# ArduinoUnoShield.net
KiCad netlist of a schematic drawn in Altium Designer
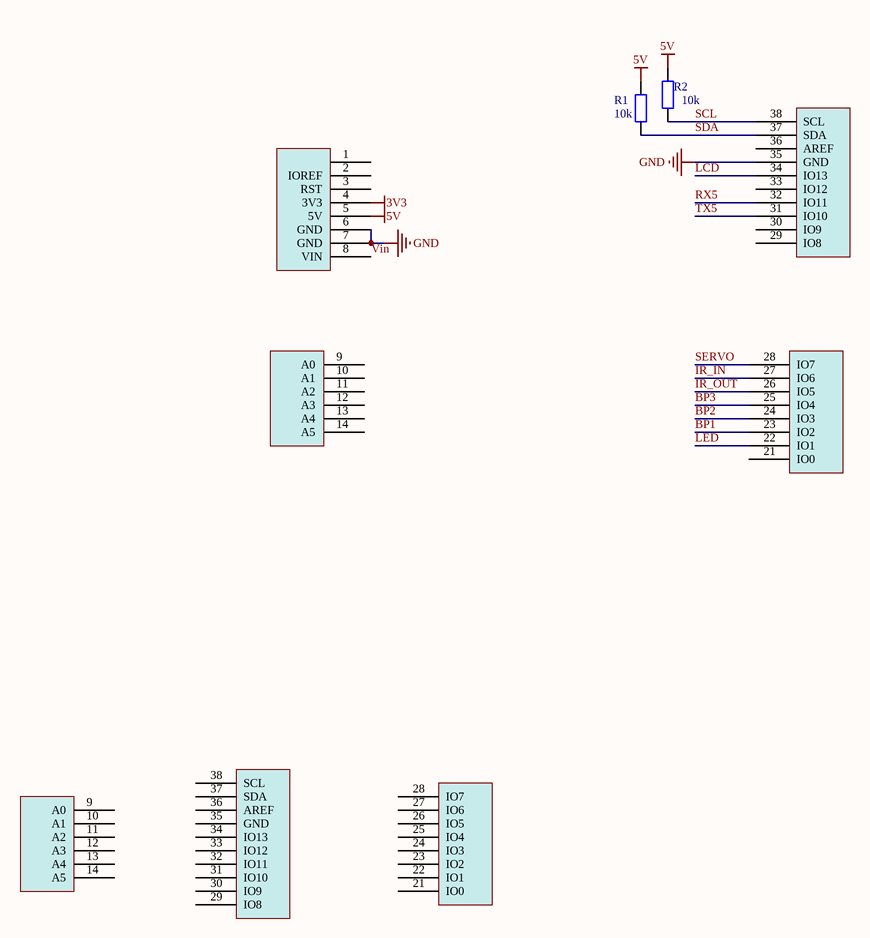
[diagram p0: ArduinoUnoShield.SchDoc]

(export (version "E")
  (design (tool "Eeschema 10.0.6"))
  (components
    (comp (ref "P1")
      (value "UNO4NUCLEO")
      (footprint "UNO4NUCLEO")
      (description "Header mâle, Carte-à-carte, 2.54 mm, 1 Rangée(s), 10 Contact(s), Traversant, droit, Série 2211S")
      (libsource (lib "MGLib_v2") (part "UNO4NUCLEO"))
    )
    (comp (ref "P1B")
      (value "UNO4NUCLEO")
      (footprint "UNO4NUCLEO")
      (description "Header mâle, Carte-à-carte, 2.54 mm, 1 Rangée(s), 10 Contact(s), Traversant, droit, Série 2211S")
      (libsource (lib "MGLib_v2") (part "UNO4NUCLEO"))
    )
    (comp (ref "P1C")
      (value "UNO4NUCLEO")
      (footprint "UNO4NUCLEO")
      (description "Header mâle, Carte-à-carte, 2.54 mm, 1 Rangée(s), 10 Contact(s), Traversant, droit, Série 2211S")
      (libsource (lib "MGLib_v2") (part "UNO4NUCLEO"))
    )
    (comp (ref "P1D")
      (value "UNO4NUCLEO")
      (footprint "UNO4NUCLEO")
      (description "Header mâle, Carte-à-carte, 2.54 mm, 1 Rangée(s), 10 Contact(s), Traversant, droit, Série 2211S")
      (libsource (lib "MGLib_v2") (part "UNO4NUCLEO"))
    )
    (comp (ref "R1")
      (value "10k")
      (footprint "0805-R")
      (description "Résistance à puce CMS, 10 kohm, ± 1%, 250 mW, 0805 [2012 Metric], Couche épaisse, Haute puissance")
      (fields (field (name "VOLTAGE") "150V"))
      (libsource (lib "GEII1") (part "Res"))
    )
    (comp (ref "R2")
      (value "10k")
      (footprint "0805-R")
      (description "Résistance à puce CMS, 10 kohm, ± 1%, 250 mW, 0805 [2012 Metric], Couche épaisse, Haute puissance")
      (fields (field (name "VOLTAGE") "150V"))
      (libsource (lib "GEII1") (part "Res"))
    )
  )
  (nets
    (net (code "1") (name "/BP1") (class "Default")
      (node (ref "P1") (pin "23") (pinfunction "IO2_23") (pintype "passive"))
    )
    (net (code "2") (name "/BP2") (class "Default")
      (node (ref "P1") (pin "24") (pinfunction "IO3_24") (pintype "passive"))
    )
    (net (code "3") (name "/BP3") (class "Default")
      (node (ref "P1") (pin "25") (pinfunction "IO4_25") (pintype "passive"))
    )
    (net (code "4") (name "/IR_IN") (class "Default")
      (node (ref "P1") (pin "27") (pinfunction "IO6_27") (pintype "passive"))
    )
    (net (code "5") (name "/IR_OUT") (class "Default")
      (node (ref "P1") (pin "26") (pinfunction "IO5_26") (pintype "passive"))
    )
    (net (code "6") (name "/LCD") (class "Default")
      (node (ref "P1") (pin "34") (pinfunction "IO13_34") (pintype "passive"))
    )
    (net (code "7") (name "/LED") (class "Default")
      (node (ref "P1") (pin "22") (pinfunction "IO1_22") (pintype "passive"))
    )
    (net (code "8") (name "/RX5") (class "Default")
      (node (ref "P1") (pin "32") (pinfunction "IO11_32") (pintype "passive"))
    )
    (net (code "9") (name "/SCL") (class "Default")
      (node (ref "P1") (pin "38") (pinfunction "SCL_38") (pintype "passive"))
      (node (ref "R2") (pin "2") (pinfunction "2_2") (pintype "passive"))
    )
    (net (code "10") (name "/SDA") (class "Default")
      (node (ref "P1") (pin "37") (pinfunction "SDA_37") (pintype "passive"))
      (node (ref "R1") (pin "2") (pinfunction "2_2") (pintype "passive"))
    )
    (net (code "11") (name "/SERVO") (class "Default")
      (node (ref "P1") (pin "28") (pinfunction "IO7_28") (pintype "passive"))
    )
    (net (code "12") (name "/TX5") (class "Default")
      (node (ref "P1") (pin "31") (pinfunction "IO10_31") (pintype "passive"))
    )
    (net (code "13") (name "/Vin") (class "Default")
      (node (ref "P1") (pin "8") (pinfunction "VIN_8") (pintype "passive"))
    )
    (net (code "14") (name "3V3") (class "Default")
      (node (ref "P1") (pin "4") (pinfunction "3V3_4") (pintype "passive"))
    )
    (net (code "15") (name "5V") (class "Default")
      (node (ref "P1") (pin "5") (pinfunction "5V_5") (pintype "passive"))
      (node (ref "R1") (pin "1") (pinfunction "1_1") (pintype "passive"))
      (node (ref "R2") (pin "1") (pinfunction "1_1") (pintype "passive"))
    )
    (net (code "16") (name "GND") (class "Default")
      (node (ref "P1") (pin "35") (pinfunction "GND_35") (pintype "passive"))
      (node (ref "P1") (pin "6") (pinfunction "GND_6") (pintype "passive"))
      (node (ref "P1") (pin "7") (pinfunction "GND_7") (pintype "passive"))
    )
    (net (code "17") (name "unconnected-(P1A-8-Pad1)") (class "Default")
      (node (ref "P1") (pin "1") (pinfunction "8_1") (pintype "passive"))
    )
    (net (code "18") (name "unconnected-(P1A-IOREF-Pad2)") (class "Default")
      (node (ref "P1") (pin "2") (pinfunction "IOREF_2") (pintype "passive"))
    )
    (net (code "19") (name "unconnected-(P1A-RST-Pad3)") (class "Default")
      (node (ref "P1") (pin "3") (pinfunction "RST_3") (pintype "passive"))
    )
    (net (code "20") (name "unconnected-(P1B-A0-Pad9)") (class "Default")
      (node (ref "P1") (pin "9") (pinfunction "A0_9") (pintype "passive"))
    )
    (net (code "21") (name "unconnected-(P1B-A1-Pad10)") (class "Default")
      (node (ref "P1") (pin "10") (pinfunction "A1_10") (pintype "passive"))
    )
    (net (code "22") (name "unconnected-(P1B-A2-Pad11)") (class "Default")
      (node (ref "P1") (pin "11") (pinfunction "A2_11") (pintype "passive"))
    )
    (net (code "23") (name "unconnected-(P1B-A3-Pad12)") (class "Default")
      (node (ref "P1") (pin "12") (pinfunction "A3_12") (pintype "passive"))
    )
    (net (code "24") (name "unconnected-(P1B-A4-Pad13)") (class "Default")
      (node (ref "P1") (pin "13") (pinfunction "A4_13") (pintype "passive"))
    )
    (net (code "25") (name "unconnected-(P1B-A5-Pad14)") (class "Default")
      (node (ref "P1") (pin "14") (pinfunction "A5_14") (pintype "passive"))
    )
    (net (code "26") (name "unconnected-(P1BB-A0-Pad9)") (class "Default")
      (node (ref "P1B") (pin "9") (pinfunction "A0_9") (pintype "passive"))
    )
    (net (code "27") (name "unconnected-(P1BB-A1-Pad10)") (class "Default")
      (node (ref "P1B") (pin "10") (pinfunction "A1_10") (pintype "passive"))
    )
    (net (code "28") (name "unconnected-(P1BB-A2-Pad11)") (class "Default")
      (node (ref "P1B") (pin "11") (pinfunction "A2_11") (pintype "passive"))
    )
    (net (code "29") (name "unconnected-(P1BB-A3-Pad12)") (class "Default")
      (node (ref "P1B") (pin "12") (pinfunction "A3_12") (pintype "passive"))
    )
    (net (code "30") (name "unconnected-(P1BB-A4-Pad13)") (class "Default")
      (node (ref "P1B") (pin "13") (pinfunction "A4_13") (pintype "passive"))
    )
    (net (code "31") (name "unconnected-(P1BB-A5-Pad14)") (class "Default")
      (node (ref "P1B") (pin "14") (pinfunction "A5_14") (pintype "passive"))
    )
    (net (code "32") (name "unconnected-(P1C-IO0-Pad21)") (class "Default")
      (node (ref "P1") (pin "21") (pinfunction "IO0_21") (pintype "passive"))
    )
    (net (code "33") (name "unconnected-(P1CD-AREF-Pad36)") (class "Default")
      (node (ref "P1C") (pin "36") (pinfunction "AREF_36") (pintype "passive"))
    )
    (net (code "34") (name "unconnected-(P1CD-GND-Pad35)") (class "Default")
      (node (ref "P1C") (pin "35") (pinfunction "GND_35") (pintype "passive"))
    )
    (net (code "35") (name "unconnected-(P1CD-IO8-Pad29)") (class "Default")
      (node (ref "P1C") (pin "29") (pinfunction "IO8_29") (pintype "passive"))
    )
    (net (code "36") (name "unconnected-(P1CD-IO9-Pad30)") (class "Default")
      (node (ref "P1C") (pin "30") (pinfunction "IO9_30") (pintype "passive"))
    )
    (net (code "37") (name "unconnected-(P1CD-IO10-Pad31)") (class "Default")
      (node (ref "P1C") (pin "31") (pinfunction "IO10_31") (pintype "passive"))
    )
    (net (code "38") (name "unconnected-(P1CD-IO11-Pad32)") (class "Default")
      (node (ref "P1C") (pin "32") (pinfunction "IO11_32") (pintype "passive"))
    )
    (net (code "39") (name "unconnected-(P1CD-IO12-Pad33)") (class "Default")
      (node (ref "P1C") (pin "33") (pinfunction "IO12_33") (pintype "passive"))
    )
    (net (code "40") (name "unconnected-(P1CD-IO13-Pad34)") (class "Default")
      (node (ref "P1C") (pin "34") (pinfunction "IO13_34") (pintype "passive"))
    )
    (net (code "41") (name "unconnected-(P1CD-SCL-Pad38)") (class "Default")
      (node (ref "P1C") (pin "38") (pinfunction "SCL_38") (pintype "passive"))
    )
    (net (code "42") (name "unconnected-(P1CD-SDA-Pad37)") (class "Default")
      (node (ref "P1C") (pin "37") (pinfunction "SDA_37") (pintype "passive"))
    )
    (net (code "43") (name "unconnected-(P1D-AREF-Pad36)") (class "Default")
      (node (ref "P1") (pin "36") (pinfunction "AREF_36") (pintype "passive"))
    )
    (net (code "44") (name "unconnected-(P1D-IO8-Pad29)") (class "Default")
      (node (ref "P1") (pin "29") (pinfunction "IO8_29") (pintype "passive"))
    )
    (net (code "45") (name "unconnected-(P1D-IO9-Pad30)") (class "Default")
      (node (ref "P1") (pin "30") (pinfunction "IO9_30") (pintype "passive"))
    )
    (net (code "46") (name "unconnected-(P1D-IO12-Pad33)") (class "Default")
      (node (ref "P1") (pin "33") (pinfunction "IO12_33") (pintype "passive"))
    )
    (net (code "47") (name "unconnected-(P1DC-IO0-Pad21)") (class "Default")
      (node (ref "P1D") (pin "21") (pinfunction "IO0_21") (pintype "passive"))
    )
    (net (code "48") (name "unconnected-(P1DC-IO1-Pad22)") (class "Default")
      (node (ref "P1D") (pin "22") (pinfunction "IO1_22") (pintype "passive"))
    )
    (net (code "49") (name "unconnected-(P1DC-IO2-Pad23)") (class "Default")
      (node (ref "P1D") (pin "23") (pinfunction "IO2_23") (pintype "passive"))
    )
    (net (code "50") (name "unconnected-(P1DC-IO3-Pad24)") (class "Default")
      (node (ref "P1D") (pin "24") (pinfunction "IO3_24") (pintype "passive"))
    )
    (net (code "51") (name "unconnected-(P1DC-IO4-Pad25)") (class "Default")
      (node (ref "P1D") (pin "25") (pinfunction "IO4_25") (pintype "passive"))
    )
    (net (code "52") (name "unconnected-(P1DC-IO5-Pad26)") (class "Default")
      (node (ref "P1D") (pin "26") (pinfunction "IO5_26") (pintype "passive"))
    )
    (net (code "53") (name "unconnected-(P1DC-IO6-Pad27)") (class "Default")
      (node (ref "P1D") (pin "27") (pinfunction "IO6_27") (pintype "passive"))
    )
    (net (code "54") (name "unconnected-(P1DC-IO7-Pad28)") (class "Default")
      (node (ref "P1D") (pin "28") (pinfunction "IO7_28") (pintype "passive"))
    )
  )
)
